# raspi-avr-teletext-2side.net
KiCad netlist of a schematic drawn in EAGLE
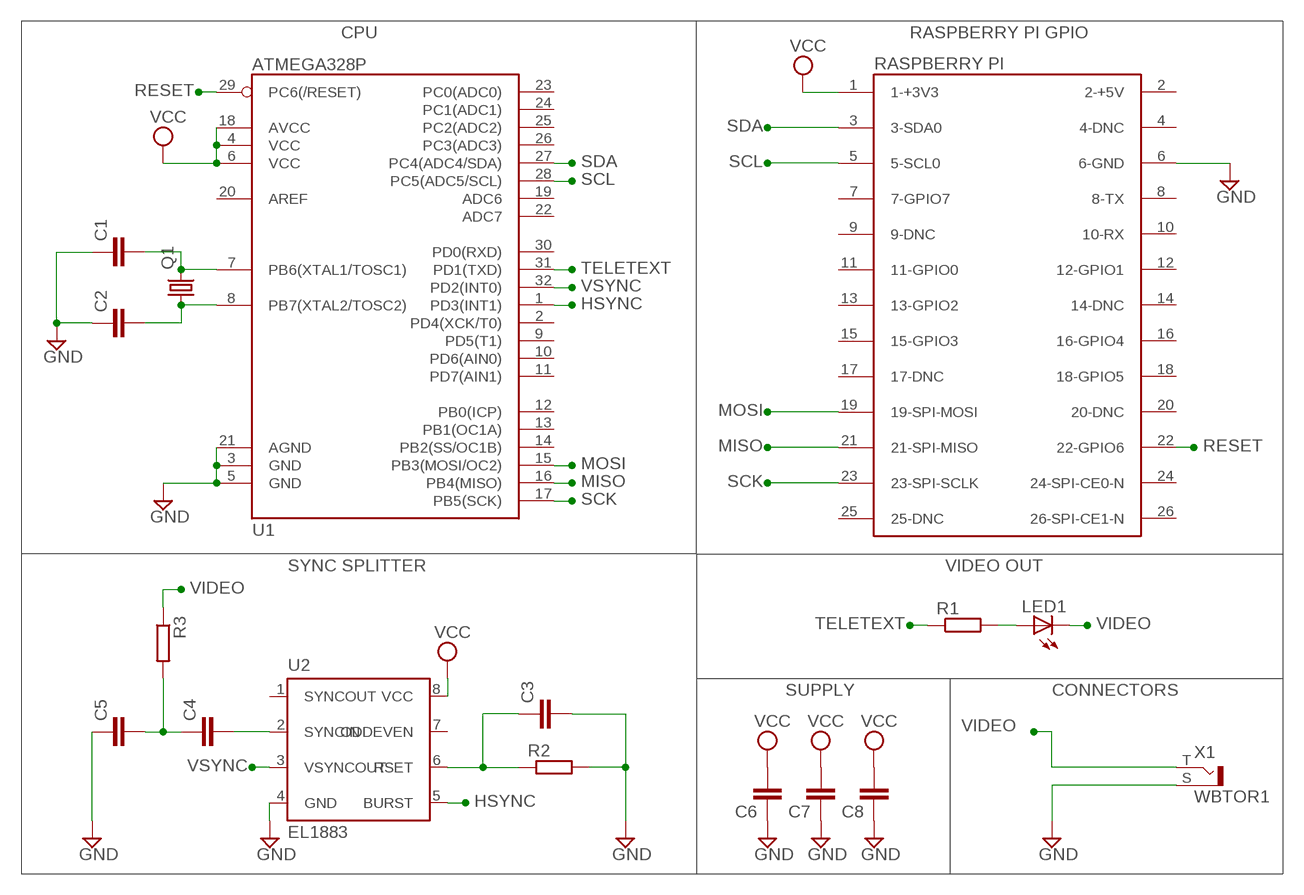
[diagram p0: schematic, sheet 1]

(export (version "E")
  (design (tool "Eeschema 10.0.6"))
  (components
    (comp (ref "C1")
      (value "C-EUC0603")
      (footprint "eagle-import:C0603")
      (libsource (lib "eagle-import") (part "C-EUC0603"))
    )
    (comp (ref "C2")
      (value "C-EUC0603")
      (footprint "eagle-import:C0603")
      (libsource (lib "eagle-import") (part "C-EUC0603"))
    )
    (comp (ref "C3")
      (value "C-EUC0603")
      (footprint "eagle-import:C0603")
      (libsource (lib "eagle-import") (part "C-EUC0603"))
    )
    (comp (ref "C4")
      (value "C-EUC0603")
      (footprint "eagle-import:C0603")
      (libsource (lib "eagle-import") (part "C-EUC0603"))
    )
    (comp (ref "C5")
      (value "C-EUC0603")
      (footprint "eagle-import:C0603")
      (libsource (lib "eagle-import") (part "C-EUC0603"))
    )
    (comp (ref "C6")
      (value "C-EUC0603")
      (footprint "eagle-import:C0603")
      (libsource (lib "eagle-import") (part "C-EUC0603"))
    )
    (comp (ref "C7")
      (value "C-EUC0603")
      (footprint "eagle-import:C0603")
      (libsource (lib "eagle-import") (part "C-EUC0603"))
    )
    (comp (ref "C8")
      (value "C-EUC0603")
      (footprint "eagle-import:C0603")
      (libsource (lib "eagle-import") (part "C-EUC0603"))
    )
    (comp (ref "D1")
      (value "RASPBERRY-PI")
      (footprint "eagle-import:RASPBERRY-PI")
      (libsource (lib "eagle-import") (part "RASPBERRY-PI"))
    )
    (comp (ref "LED1")
      (value "LEDCHIP-LED0603")
      (footprint "eagle-import:CHIP-LED0603")
      (libsource (lib "eagle-import") (part "LEDCHIP-LED0603"))
    )
    (comp (ref "Q1")
      (value "CRYSTALHC49U-V")
      (footprint "eagle-import:HC49U-V")
      (libsource (lib "eagle-import") (part "CRYSTALHC49U-V"))
    )
    (comp (ref "R1")
      (value "R-EU_R0603")
      (footprint "eagle-import:R0603")
      (libsource (lib "eagle-import") (part "R-EU_R0603"))
    )
    (comp (ref "R2")
      (value "R-EU_R0603")
      (footprint "eagle-import:R0603")
      (libsource (lib "eagle-import") (part "R-EU_R0603"))
    )
    (comp (ref "R3")
      (value "R-EU_R0603")
      (footprint "eagle-import:R0603")
      (libsource (lib "eagle-import") (part "R-EU_R0603"))
    )
    (comp (ref "U1")
      (value "ATMEGA328P")
      (footprint "eagle-import:TQFP32-08")
      (libsource (lib "eagle-import") (part "ATMEGA328_SMT"))
    )
    (comp (ref "U2")
      (value "EL1883")
      (footprint "eagle-import:SOIC8")
      (libsource (lib "eagle-import") (part "LM1881M"))
    )
    (comp (ref "X1")
      (value "WBTOR1")
      (footprint "eagle-import:WBTOR1")
      (fields (field (name "MPN") "WBTOR 1 BLACK"))
      (libsource (lib "eagle-import") (part "WBTOR1"))
    )
  )
  (nets
    (net (code "1") (name "/HSYNC") (class "Default")
      (node (ref "U1") (pin "1") (pinfunction "PD3(INT1)_1") (pintype "bidirectional"))
      (node (ref "U2") (pin "5") (pinfunction "BURST_5") (pintype "output"))
    )
    (net (code "2") (name "/MISO") (class "Default")
      (node (ref "D1") (pin "21") (pinfunction "21-SPI-MISO_21") (pintype "bidirectional"))
      (node (ref "U1") (pin "16") (pinfunction "PB4(MISO)_16") (pintype "bidirectional"))
    )
    (net (code "3") (name "/MOSI") (class "Default")
      (node (ref "D1") (pin "19") (pinfunction "19-SPI-MOSI_19") (pintype "bidirectional"))
      (node (ref "U1") (pin "15") (pinfunction "PB3(MOSI/OC2)_15") (pintype "bidirectional"))
    )
    (net (code "4") (name "/RESET") (class "Default")
      (node (ref "D1") (pin "22") (pinfunction "22-GPIO6_22") (pintype "bidirectional"))
      (node (ref "U1") (pin "29") (pinfunction "PC6(/RESET)_29") (pintype "bidirectional"))
    )
    (net (code "5") (name "/SCK") (class "Default")
      (node (ref "D1") (pin "23") (pinfunction "23-SPI-SCLK_23") (pintype "bidirectional"))
      (node (ref "U1") (pin "17") (pinfunction "PB5(SCK)_17") (pintype "bidirectional"))
    )
    (net (code "6") (name "/SCL") (class "Default")
      (node (ref "D1") (pin "5") (pinfunction "5-SCL0_5") (pintype "bidirectional"))
      (node (ref "U1") (pin "28") (pinfunction "PC5(ADC5/SCL)_28") (pintype "bidirectional"))
    )
    (net (code "7") (name "/SDA") (class "Default")
      (node (ref "D1") (pin "3") (pinfunction "3-SDA0_3") (pintype "bidirectional"))
      (node (ref "U1") (pin "27") (pinfunction "PC4(ADC4/SDA)_27") (pintype "bidirectional"))
    )
    (net (code "8") (name "/TELETEXT") (class "Default")
      (node (ref "R1") (pin "1") (pinfunction "1_1") (pintype "passive"))
      (node (ref "U1") (pin "31") (pinfunction "PD1(TXD)_31") (pintype "bidirectional"))
    )
    (net (code "9") (name "/VIDEO") (class "Default")
      (node (ref "LED1") (pin "C") (pinfunction "C_C") (pintype "passive"))
      (node (ref "R3") (pin "1") (pinfunction "1_1") (pintype "passive"))
      (node (ref "X1") (pin "T") (pinfunction "T_T") (pintype "passive"))
    )
    (net (code "10") (name "/VSYNC") (class "Default")
      (node (ref "U1") (pin "32") (pinfunction "PD2(INT0)_32") (pintype "bidirectional"))
      (node (ref "U2") (pin "3") (pinfunction "VSYNCOUT_3") (pintype "output"))
    )
    (net (code "11") (name "GND") (class "Default")
      (node (ref "C1") (pin "1") (pinfunction "1_1") (pintype "passive"))
      (node (ref "C2") (pin "1") (pinfunction "1_1") (pintype "passive"))
      (node (ref "C3") (pin "2") (pinfunction "2_2") (pintype "passive"))
      (node (ref "C5") (pin "1") (pinfunction "1_1") (pintype "passive"))
      (node (ref "C6") (pin "1") (pinfunction "1_1") (pintype "passive"))
      (node (ref "C7") (pin "1") (pinfunction "1_1") (pintype "passive"))
      (node (ref "C8") (pin "1") (pinfunction "1_1") (pintype "passive"))
      (node (ref "D1") (pin "6") (pinfunction "6-GND_6") (pintype "bidirectional"))
      (node (ref "R2") (pin "2") (pinfunction "2_2") (pintype "passive"))
      (node (ref "U1") (pin "21") (pinfunction "AGND_21") (pintype "bidirectional"))
      (node (ref "U1") (pin "3") (pinfunction "GND_3") (pintype "bidirectional"))
      (node (ref "U1") (pin "5") (pinfunction "GND_5") (pintype "bidirectional"))
      (node (ref "U2") (pin "4") (pinfunction "GND_4") (pintype "power_in"))
      (node (ref "X1") (pin "S") (pinfunction "S_S") (pintype "passive"))
    )
    (net (code "12") (name "Net-(C4-Pad1)") (class "Default")
      (node (ref "C4") (pin "1") (pinfunction "1_1") (pintype "passive"))
      (node (ref "C5") (pin "2") (pinfunction "2_2") (pintype "passive"))
      (node (ref "R3") (pin "2") (pinfunction "2_2") (pintype "passive"))
    )
    (net (code "13") (name "Net-(LED1-PadA)") (class "Default")
      (node (ref "LED1") (pin "A") (pinfunction "A_A") (pintype "passive"))
      (node (ref "R1") (pin "2") (pinfunction "2_2") (pintype "passive"))
    )
    (net (code "14") (name "Net-(U1-PB6(XTAL1{slash}TOSC1))") (class "Default")
      (node (ref "C1") (pin "2") (pinfunction "2_2") (pintype "passive"))
      (node (ref "Q1") (pin "2") (pinfunction "2_2") (pintype "passive"))
      (node (ref "U1") (pin "7") (pinfunction "PB6(XTAL1/TOSC1)_7") (pintype "bidirectional"))
    )
    (net (code "15") (name "Net-(U1-PB7(XTAL2{slash}TOSC2))") (class "Default")
      (node (ref "C2") (pin "2") (pinfunction "2_2") (pintype "passive"))
      (node (ref "Q1") (pin "1") (pinfunction "1_1") (pintype "passive"))
      (node (ref "U1") (pin "8") (pinfunction "PB7(XTAL2/TOSC2)_8") (pintype "bidirectional"))
    )
    (net (code "16") (name "Net-(U2-RSET)") (class "Default")
      (node (ref "C3") (pin "1") (pinfunction "1_1") (pintype "passive"))
      (node (ref "R2") (pin "1") (pinfunction "1_1") (pintype "passive"))
      (node (ref "U2") (pin "6") (pinfunction "RSET_6") (pintype "output"))
    )
    (net (code "17") (name "Net-(U2-SYNCIN)") (class "Default")
      (node (ref "C4") (pin "2") (pinfunction "2_2") (pintype "passive"))
      (node (ref "U2") (pin "2") (pinfunction "SYNCIN_2") (pintype "input"))
    )
    (net (code "18") (name "VCC") (class "Default")
      (node (ref "C6") (pin "2") (pinfunction "2_2") (pintype "passive"))
      (node (ref "C7") (pin "2") (pinfunction "2_2") (pintype "passive"))
      (node (ref "C8") (pin "2") (pinfunction "2_2") (pintype "passive"))
      (node (ref "D1") (pin "1") (pinfunction "1-+3V3_1") (pintype "bidirectional"))
      (node (ref "U1") (pin "18") (pinfunction "AVCC_18") (pintype "bidirectional"))
      (node (ref "U1") (pin "4") (pinfunction "VCC_4") (pintype "bidirectional"))
      (node (ref "U1") (pin "6") (pinfunction "VCC_6") (pintype "bidirectional"))
      (node (ref "U2") (pin "8") (pinfunction "VCC_8") (pintype "power_in"))
    )
    (net (code "19") (name "unconnected-(D1-2-+5V-Pad2)") (class "Default")
      (node (ref "D1") (pin "2") (pinfunction "2-+5V_2") (pintype "bidirectional"))
    )
    (net (code "20") (name "unconnected-(D1-4-DNC-Pad4)") (class "Default")
      (node (ref "D1") (pin "4") (pinfunction "4-DNC_4") (pintype "bidirectional"))
    )
    (net (code "21") (name "unconnected-(D1-7-GPIO7-Pad7)") (class "Default")
      (node (ref "D1") (pin "7") (pinfunction "7-GPIO7_7") (pintype "bidirectional"))
    )
    (net (code "22") (name "unconnected-(D1-8-TX-Pad8)") (class "Default")
      (node (ref "D1") (pin "8") (pinfunction "8-TX_8") (pintype "bidirectional"))
    )
    (net (code "23") (name "unconnected-(D1-9-DNC-Pad9)") (class "Default")
      (node (ref "D1") (pin "9") (pinfunction "9-DNC_9") (pintype "bidirectional"))
    )
    (net (code "24") (name "unconnected-(D1-10-RX-Pad10)") (class "Default")
      (node (ref "D1") (pin "10") (pinfunction "10-RX_10") (pintype "bidirectional"))
    )
    (net (code "25") (name "unconnected-(D1-11-GPIO0-Pad11)") (class "Default")
      (node (ref "D1") (pin "11") (pinfunction "11-GPIO0_11") (pintype "bidirectional"))
    )
    (net (code "26") (name "unconnected-(D1-12-GPIO1-Pad12)") (class "Default")
      (node (ref "D1") (pin "12") (pinfunction "12-GPIO1_12") (pintype "bidirectional"))
    )
    (net (code "27") (name "unconnected-(D1-13-GPIO2-Pad13)") (class "Default")
      (node (ref "D1") (pin "13") (pinfunction "13-GPIO2_13") (pintype "bidirectional"))
    )
    (net (code "28") (name "unconnected-(D1-14-DNC-Pad14)") (class "Default")
      (node (ref "D1") (pin "14") (pinfunction "14-DNC_14") (pintype "bidirectional"))
    )
    (net (code "29") (name "unconnected-(D1-15-GPIO3-Pad15)") (class "Default")
      (node (ref "D1") (pin "15") (pinfunction "15-GPIO3_15") (pintype "bidirectional"))
    )
    (net (code "30") (name "unconnected-(D1-16-GPIO4-Pad16)") (class "Default")
      (node (ref "D1") (pin "16") (pinfunction "16-GPIO4_16") (pintype "bidirectional"))
    )
    (net (code "31") (name "unconnected-(D1-17-DNC-Pad17)") (class "Default")
      (node (ref "D1") (pin "17") (pinfunction "17-DNC_17") (pintype "bidirectional"))
    )
    (net (code "32") (name "unconnected-(D1-18-GPIO5-Pad18)") (class "Default")
      (node (ref "D1") (pin "18") (pinfunction "18-GPIO5_18") (pintype "bidirectional"))
    )
    (net (code "33") (name "unconnected-(D1-20-DNC-Pad20)") (class "Default")
      (node (ref "D1") (pin "20") (pinfunction "20-DNC_20") (pintype "bidirectional"))
    )
    (net (code "34") (name "unconnected-(D1-24-SPI-CE0-N-Pad24)") (class "Default")
      (node (ref "D1") (pin "24") (pinfunction "24-SPI-CE0-N_24") (pintype "bidirectional"))
    )
    (net (code "35") (name "unconnected-(D1-25-DNC-Pad25)") (class "Default")
      (node (ref "D1") (pin "25") (pinfunction "25-DNC_25") (pintype "bidirectional"))
    )
    (net (code "36") (name "unconnected-(D1-26-SPI-CE1-N-Pad26)") (class "Default")
      (node (ref "D1") (pin "26") (pinfunction "26-SPI-CE1-N_26") (pintype "bidirectional"))
    )
    (net (code "37") (name "unconnected-(U1-ADC6-Pad19)") (class "Default")
      (node (ref "U1") (pin "19") (pinfunction "ADC6_19") (pintype "bidirectional"))
    )
    (net (code "38") (name "unconnected-(U1-ADC7-Pad22)") (class "Default")
      (node (ref "U1") (pin "22") (pinfunction "ADC7_22") (pintype "bidirectional"))
    )
    (net (code "39") (name "unconnected-(U1-AREF-Pad20)") (class "Default")
      (node (ref "U1") (pin "20") (pinfunction "AREF_20") (pintype "bidirectional"))
    )
    (net (code "40") (name "unconnected-(U1-PB0(ICP)-Pad12)") (class "Default")
      (node (ref "U1") (pin "12") (pinfunction "PB0(ICP)_12") (pintype "bidirectional"))
    )
    (net (code "41") (name "unconnected-(U1-PB1(OC1A)-Pad13)") (class "Default")
      (node (ref "U1") (pin "13") (pinfunction "PB1(OC1A)_13") (pintype "bidirectional"))
    )
    (net (code "42") (name "unconnected-(U1-PB2(SS{slash}OC1B)-Pad14)") (class "Default")
      (node (ref "U1") (pin "14") (pinfunction "PB2(SS/OC1B)_14") (pintype "bidirectional"))
    )
    (net (code "43") (name "unconnected-(U1-PC0(ADC0)-Pad23)") (class "Default")
      (node (ref "U1") (pin "23") (pinfunction "PC0(ADC0)_23") (pintype "bidirectional"))
    )
    (net (code "44") (name "unconnected-(U1-PC1(ADC1)-Pad24)") (class "Default")
      (node (ref "U1") (pin "24") (pinfunction "PC1(ADC1)_24") (pintype "bidirectional"))
    )
    (net (code "45") (name "unconnected-(U1-PC2(ADC2)-Pad25)") (class "Default")
      (node (ref "U1") (pin "25") (pinfunction "PC2(ADC2)_25") (pintype "bidirectional"))
    )
    (net (code "46") (name "unconnected-(U1-PC3(ADC3)-Pad26)") (class "Default")
      (node (ref "U1") (pin "26") (pinfunction "PC3(ADC3)_26") (pintype "bidirectional"))
    )
    (net (code "47") (name "unconnected-(U1-PD0(RXD)-Pad30)") (class "Default")
      (node (ref "U1") (pin "30") (pinfunction "PD0(RXD)_30") (pintype "bidirectional"))
    )
    (net (code "48") (name "unconnected-(U1-PD4(XCK{slash}T0)-Pad2)") (class "Default")
      (node (ref "U1") (pin "2") (pinfunction "PD4(XCK/T0)_2") (pintype "bidirectional"))
    )
    (net (code "49") (name "unconnected-(U1-PD5(T1)-Pad9)") (class "Default")
      (node (ref "U1") (pin "9") (pinfunction "PD5(T1)_9") (pintype "bidirectional"))
    )
    (net (code "50") (name "unconnected-(U1-PD6(AIN0)-Pad10)") (class "Default")
      (node (ref "U1") (pin "10") (pinfunction "PD6(AIN0)_10") (pintype "bidirectional"))
    )
    (net (code "51") (name "unconnected-(U1-PD7(AIN1)-Pad11)") (class "Default")
      (node (ref "U1") (pin "11") (pinfunction "PD7(AIN1)_11") (pintype "bidirectional"))
    )
    (net (code "52") (name "unconnected-(U2-ODDEVEN-Pad7)") (class "Default")
      (node (ref "U2") (pin "7") (pinfunction "ODDEVEN_7") (pintype "output"))
    )
    (net (code "53") (name "unconnected-(U2-SYNCOUT-Pad1)") (class "Default")
      (node (ref "U2") (pin "1") (pinfunction "SYNCOUT_1") (pintype "output"))
    )
  )
)
